# Y1BVER2_0_3.net
KiCad netlist of a schematic drawn in Altium Designer
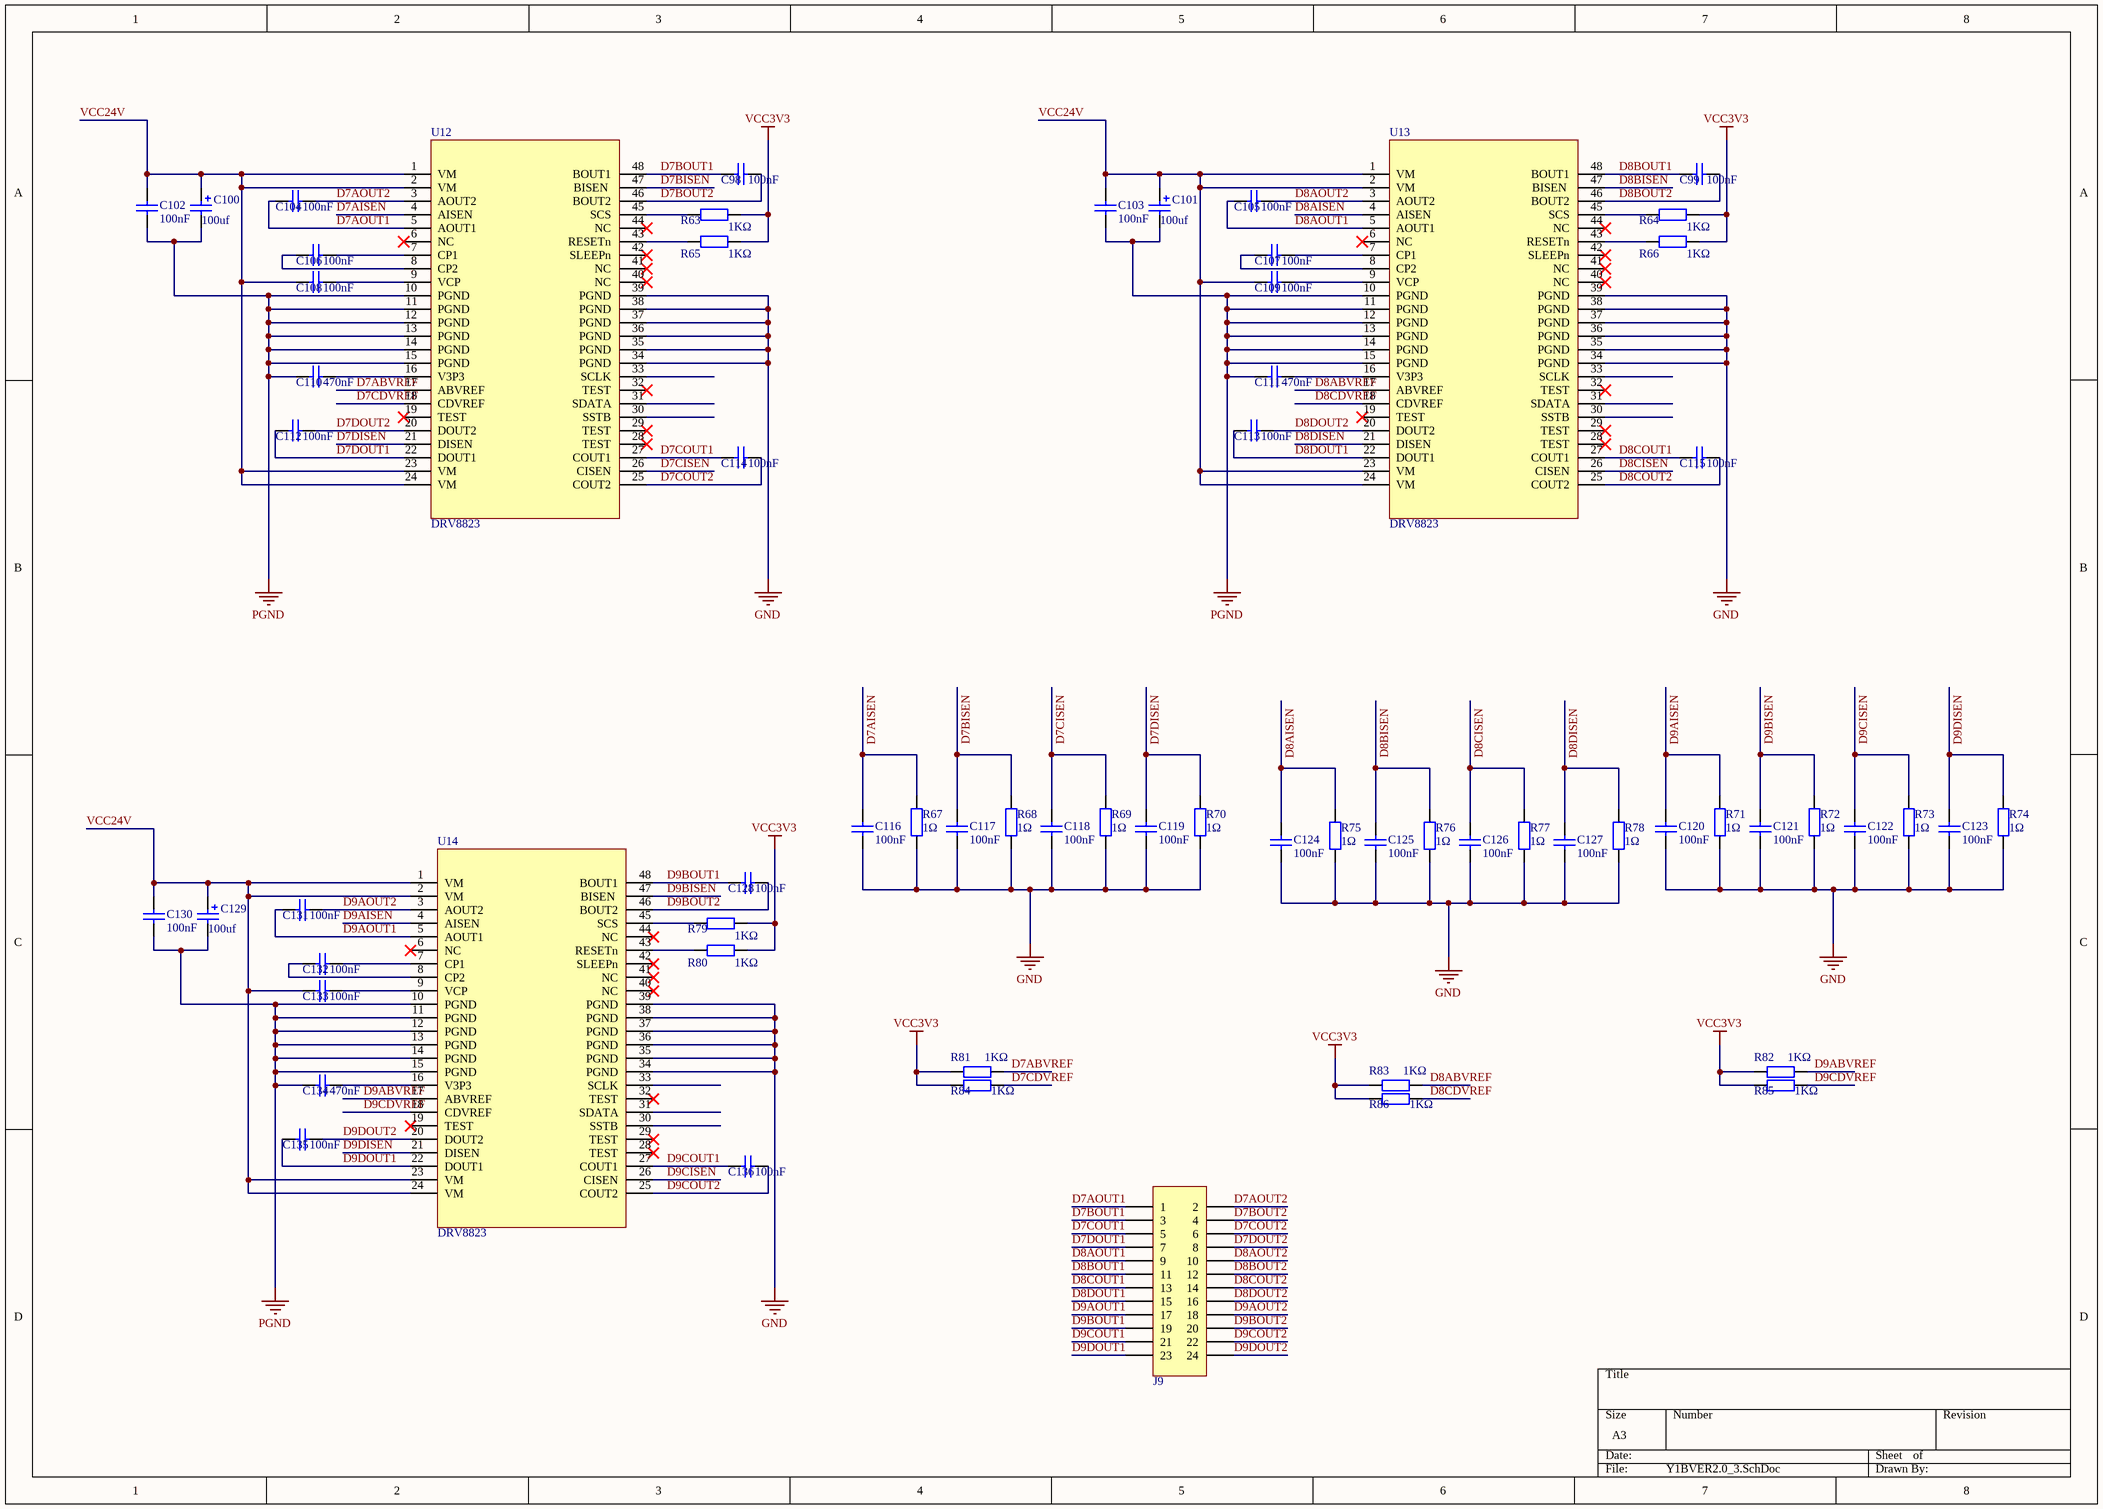
[diagram p0: Y1BVER2.0_3.SchDoc]

(export (version "E")
  (design (tool "Eeschema 10.0.6"))
  (components
    (comp (ref "C98")
      (value "100nF")
      (footprint "0603_C")
      (description "贴片电容")
      (libsource (lib "AD封装2018.9.19Miscellaneous Devices LC") (part "0603 100nF (104) 10% 50V"))
    )
    (comp (ref "C99")
      (value "100nF")
      (footprint "0603_C")
      (description "贴片电容")
      (libsource (lib "AD封装2018.9.19Miscellaneous Devices LC") (part "0603 100nF (104) 10% 50V"))
    )
    (comp (ref "C100") (value "100uf") (footprint "E_6.3*5.4") (libsource (lib "我的集成库") (part "C")))
    (comp (ref "C101") (value "100uf") (footprint "E_6.3*5.4") (libsource (lib "我的集成库") (part "C")))
    (comp (ref "C102")
      (value "100nF")
      (footprint "0603_C")
      (description "贴片电容")
      (libsource (lib "AD封装2018.9.19Miscellaneous Devices LC") (part "0603 100nF (104) 10% 50V"))
    )
    (comp (ref "C103")
      (value "100nF")
      (footprint "0603_C")
      (description "贴片电容")
      (libsource (lib "AD封装2018.9.19Miscellaneous Devices LC") (part "0603 100nF (104) 10% 50V"))
    )
    (comp (ref "C104")
      (value "100nF")
      (footprint "0603_C")
      (description "贴片电容")
      (libsource (lib "AD封装2018.9.19Miscellaneous Devices LC") (part "0603 100nF (104) 10% 50V"))
    )
    (comp (ref "C105")
      (value "100nF")
      (footprint "0603_C")
      (description "贴片电容")
      (libsource (lib "AD封装2018.9.19Miscellaneous Devices LC") (part "0603 100nF (104) 10% 50V"))
    )
    (comp (ref "C106")
      (value "100nF")
      (footprint "0603_C")
      (description "贴片电容")
      (libsource (lib "AD封装2018.9.19Miscellaneous Devices LC") (part "0603 100nF (104) 10% 50V"))
    )
    (comp (ref "C107")
      (value "100nF")
      (footprint "0603_C")
      (description "贴片电容")
      (libsource (lib "AD封装2018.9.19Miscellaneous Devices LC") (part "0603 100nF (104) 10% 50V"))
    )
    (comp (ref "C108")
      (value "100nF")
      (footprint "0603_C")
      (description "贴片电容")
      (libsource (lib "AD封装2018.9.19Miscellaneous Devices LC") (part "0603 100nF (104) 10% 50V"))
    )
    (comp (ref "C109")
      (value "100nF")
      (footprint "0603_C")
      (description "贴片电容")
      (libsource (lib "AD封装2018.9.19Miscellaneous Devices LC") (part "0603 100nF (104) 10% 50V"))
    )
    (comp (ref "C110")
      (value "470nF")
      (footprint "0603_C")
      (description "贴片电容")
      (libsource (lib "AD封装2018.9.19Miscellaneous Devices LC") (part "0603 470nF (474) 10% 25V"))
    )
    (comp (ref "C111")
      (value "470nF")
      (footprint "0603_C")
      (description "贴片电容")
      (libsource (lib "AD封装2018.9.19Miscellaneous Devices LC") (part "0603 470nF (474) 10% 25V"))
    )
    (comp (ref "C112")
      (value "100nF")
      (footprint "0603_C")
      (description "贴片电容")
      (libsource (lib "AD封装2018.9.19Miscellaneous Devices LC") (part "0603 100nF (104) 10% 50V"))
    )
    (comp (ref "C113")
      (value "100nF")
      (footprint "0603_C")
      (description "贴片电容")
      (libsource (lib "AD封装2018.9.19Miscellaneous Devices LC") (part "0603 100nF (104) 10% 50V"))
    )
    (comp (ref "C114")
      (value "100nF")
      (footprint "0603_C")
      (description "贴片电容")
      (libsource (lib "AD封装2018.9.19Miscellaneous Devices LC") (part "0603 100nF (104) 10% 50V"))
    )
    (comp (ref "C115")
      (value "100nF")
      (footprint "0603_C")
      (description "贴片电容")
      (libsource (lib "AD封装2018.9.19Miscellaneous Devices LC") (part "0603 100nF (104) 10% 50V"))
    )
    (comp (ref "C116")
      (value "100nF")
      (footprint "0603_C")
      (description "贴片电容")
      (libsource (lib "AD封装2018.9.19Miscellaneous Devices LC") (part "0603 100nF (104) 10% 50V"))
    )
    (comp (ref "C117")
      (value "100nF")
      (footprint "0603_C")
      (description "贴片电容")
      (libsource (lib "AD封装2018.9.19Miscellaneous Devices LC") (part "0603 100nF (104) 10% 50V"))
    )
    (comp (ref "C118")
      (value "100nF")
      (footprint "0603_C")
      (description "贴片电容")
      (libsource (lib "AD封装2018.9.19Miscellaneous Devices LC") (part "0603 100nF (104) 10% 50V"))
    )
    (comp (ref "C119")
      (value "100nF")
      (footprint "0603_C")
      (description "贴片电容")
      (libsource (lib "AD封装2018.9.19Miscellaneous Devices LC") (part "0603 100nF (104) 10% 50V"))
    )
    (comp (ref "C120")
      (value "100nF")
      (footprint "0603_C")
      (description "贴片电容")
      (libsource (lib "AD封装2018.9.19Miscellaneous Devices LC") (part "0603 100nF (104) 10% 50V"))
    )
    (comp (ref "C121")
      (value "100nF")
      (footprint "0603_C")
      (description "贴片电容")
      (libsource (lib "AD封装2018.9.19Miscellaneous Devices LC") (part "0603 100nF (104) 10% 50V"))
    )
    (comp (ref "C122")
      (value "100nF")
      (footprint "0603_C")
      (description "贴片电容")
      (libsource (lib "AD封装2018.9.19Miscellaneous Devices LC") (part "0603 100nF (104) 10% 50V"))
    )
    (comp (ref "C123")
      (value "100nF")
      (footprint "0603_C")
      (description "贴片电容")
      (libsource (lib "AD封装2018.9.19Miscellaneous Devices LC") (part "0603 100nF (104) 10% 50V"))
    )
    (comp (ref "C124")
      (value "100nF")
      (footprint "0603_C")
      (description "贴片电容")
      (libsource (lib "AD封装2018.9.19Miscellaneous Devices LC") (part "0603 100nF (104) 10% 50V"))
    )
    (comp (ref "C125")
      (value "100nF")
      (footprint "0603_C")
      (description "贴片电容")
      (libsource (lib "AD封装2018.9.19Miscellaneous Devices LC") (part "0603 100nF (104) 10% 50V"))
    )
    (comp (ref "C126")
      (value "100nF")
      (footprint "0603_C")
      (description "贴片电容")
      (libsource (lib "AD封装2018.9.19Miscellaneous Devices LC") (part "0603 100nF (104) 10% 50V"))
    )
    (comp (ref "C127")
      (value "100nF")
      (footprint "0603_C")
      (description "贴片电容")
      (libsource (lib "AD封装2018.9.19Miscellaneous Devices LC") (part "0603 100nF (104) 10% 50V"))
    )
    (comp (ref "C128")
      (value "100nF")
      (footprint "0603_C")
      (description "贴片电容")
      (libsource (lib "AD封装2018.9.19Miscellaneous Devices LC") (part "0603 100nF (104) 10% 50V"))
    )
    (comp (ref "C129") (value "100uf") (footprint "E_6.3*5.4") (libsource (lib "我的集成库") (part "C")))
    (comp (ref "C130")
      (value "100nF")
      (footprint "0603_C")
      (description "贴片电容")
      (libsource (lib "AD封装2018.9.19Miscellaneous Devices LC") (part "0603 100nF (104) 10% 50V"))
    )
    (comp (ref "C131")
      (value "100nF")
      (footprint "0603_C")
      (description "贴片电容")
      (libsource (lib "AD封装2018.9.19Miscellaneous Devices LC") (part "0603 100nF (104) 10% 50V"))
    )
    (comp (ref "C132")
      (value "100nF")
      (footprint "0603_C")
      (description "贴片电容")
      (libsource (lib "AD封装2018.9.19Miscellaneous Devices LC") (part "0603 100nF (104) 10% 50V"))
    )
    (comp (ref "C133")
      (value "100nF")
      (footprint "0603_C")
      (description "贴片电容")
      (libsource (lib "AD封装2018.9.19Miscellaneous Devices LC") (part "0603 100nF (104) 10% 50V"))
    )
    (comp (ref "C134")
      (value "470nF")
      (footprint "0603_C")
      (description "贴片电容")
      (libsource (lib "AD封装2018.9.19Miscellaneous Devices LC") (part "0603 470nF (474) 10% 25V"))
    )
    (comp (ref "C135")
      (value "100nF")
      (footprint "0603_C")
      (description "贴片电容")
      (libsource (lib "AD封装2018.9.19Miscellaneous Devices LC") (part "0603 100nF (104) 10% 50V"))
    )
    (comp (ref "C136")
      (value "100nF")
      (footprint "0603_C")
      (description "贴片电容")
      (libsource (lib "AD封装2018.9.19Miscellaneous Devices LC") (part "0603 100nF (104) 10% 50V"))
    )
    (comp (ref "J9")
      (value "header24p")
      (footprint "5557-2*12P")
      (libsource (lib "我的集成库") (part "header24p"))
    )
    (comp (ref "R63")
      (value "1KΩ")
      (footprint "0603_R")
      (description "贴片电阻")
      (libsource (lib "AD封装2018.9.19Miscellaneous Devices LC") (part "0603 1KΩ (1001) 1%"))
    )
    (comp (ref "R64")
      (value "1KΩ")
      (footprint "0603_R")
      (description "贴片电阻")
      (libsource (lib "AD封装2018.9.19Miscellaneous Devices LC") (part "0603 1KΩ (1001) 1%"))
    )
    (comp (ref "R65")
      (value "1KΩ")
      (footprint "0603_R")
      (description "贴片电阻")
      (libsource (lib "AD封装2018.9.19Miscellaneous Devices LC") (part "0603 1KΩ (1001) 1%"))
    )
    (comp (ref "R66")
      (value "1KΩ")
      (footprint "0603_R")
      (description "贴片电阻")
      (libsource (lib "AD封装2018.9.19Miscellaneous Devices LC") (part "0603 1KΩ (1001) 1%"))
    )
    (comp (ref "R67")
      (value "1Ω")
      (footprint "0603_R")
      (description "贴片电阻")
      (libsource (lib "AD封装2018.9.19Miscellaneous Devices LC") (part "0603 1Ω (1R00) 1%"))
    )
    (comp (ref "R68")
      (value "1Ω")
      (footprint "0603_R")
      (description "贴片电阻")
      (libsource (lib "AD封装2018.9.19Miscellaneous Devices LC") (part "0603 1Ω (1R00) 1%"))
    )
    (comp (ref "R69")
      (value "1Ω")
      (footprint "0603_R")
      (description "贴片电阻")
      (libsource (lib "AD封装2018.9.19Miscellaneous Devices LC") (part "0603 1Ω (1R00) 1%"))
    )
    (comp (ref "R70")
      (value "1Ω")
      (footprint "0603_R")
      (description "贴片电阻")
      (libsource (lib "AD封装2018.9.19Miscellaneous Devices LC") (part "0603 1Ω (1R00) 1%"))
    )
    (comp (ref "R71")
      (value "1Ω")
      (footprint "0603_R")
      (description "贴片电阻")
      (libsource (lib "AD封装2018.9.19Miscellaneous Devices LC") (part "0603 1Ω (1R00) 1%"))
    )
    (comp (ref "R72")
      (value "1Ω")
      (footprint "0603_R")
      (description "贴片电阻")
      (libsource (lib "AD封装2018.9.19Miscellaneous Devices LC") (part "0603 1Ω (1R00) 1%"))
    )
    (comp (ref "R73")
      (value "1Ω")
      (footprint "0603_R")
      (description "贴片电阻")
      (libsource (lib "AD封装2018.9.19Miscellaneous Devices LC") (part "0603 1Ω (1R00) 1%"))
    )
    (comp (ref "R74")
      (value "1Ω")
      (footprint "0603_R")
      (description "贴片电阻")
      (libsource (lib "AD封装2018.9.19Miscellaneous Devices LC") (part "0603 1Ω (1R00) 1%"))
    )
    (comp (ref "R75")
      (value "1Ω")
      (footprint "0603_R")
      (description "贴片电阻")
      (libsource (lib "AD封装2018.9.19Miscellaneous Devices LC") (part "0603 1Ω (1R00) 1%"))
    )
    (comp (ref "R76")
      (value "1Ω")
      (footprint "0603_R")
      (description "贴片电阻")
      (libsource (lib "AD封装2018.9.19Miscellaneous Devices LC") (part "0603 1Ω (1R00) 1%"))
    )
    (comp (ref "R77")
      (value "1Ω")
      (footprint "0603_R")
      (description "贴片电阻")
      (libsource (lib "AD封装2018.9.19Miscellaneous Devices LC") (part "0603 1Ω (1R00) 1%"))
    )
    (comp (ref "R78")
      (value "1Ω")
      (footprint "0603_R")
      (description "贴片电阻")
      (libsource (lib "AD封装2018.9.19Miscellaneous Devices LC") (part "0603 1Ω (1R00) 1%"))
    )
    (comp (ref "R79")
      (value "1KΩ")
      (footprint "0603_R")
      (description "贴片电阻")
      (libsource (lib "AD封装2018.9.19Miscellaneous Devices LC") (part "0603 1KΩ (1001) 1%"))
    )
    (comp (ref "R80")
      (value "1KΩ")
      (footprint "0603_R")
      (description "贴片电阻")
      (libsource (lib "AD封装2018.9.19Miscellaneous Devices LC") (part "0603 1KΩ (1001) 1%"))
    )
    (comp (ref "R81")
      (value "1KΩ")
      (footprint "0603_R")
      (description "贴片电阻")
      (libsource (lib "AD封装2018.9.19Miscellaneous Devices LC") (part "0603 1KΩ (1001) 1%"))
    )
    (comp (ref "R82")
      (value "1KΩ")
      (footprint "0603_R")
      (description "贴片电阻")
      (libsource (lib "AD封装2018.9.19Miscellaneous Devices LC") (part "0603 1KΩ (1001) 1%"))
    )
    (comp (ref "R83")
      (value "1KΩ")
      (footprint "0603_R")
      (description "贴片电阻")
      (libsource (lib "AD封装2018.9.19Miscellaneous Devices LC") (part "0603 1KΩ (1001) 1%"))
    )
    (comp (ref "R84")
      (value "1KΩ")
      (footprint "0603_R")
      (description "贴片电阻")
      (libsource (lib "AD封装2018.9.19Miscellaneous Devices LC") (part "0603 1KΩ (1001) 1%"))
    )
    (comp (ref "R85")
      (value "1KΩ")
      (footprint "0603_R")
      (description "贴片电阻")
      (libsource (lib "AD封装2018.9.19Miscellaneous Devices LC") (part "0603 1KΩ (1001) 1%"))
    )
    (comp (ref "R86")
      (value "1KΩ")
      (footprint "0603_R")
      (description "贴片电阻")
      (libsource (lib "AD封装2018.9.19Miscellaneous Devices LC") (part "0603 1KΩ (1001) 1%"))
    )
    (comp (ref "U12")
      (value "DRV8823")
      (footprint "HTSSOP-48")
      (description "4路BDC电机驱动")
      (libsource (lib "我的原理图库") (part "DRV8823"))
    )
    (comp (ref "U13")
      (value "DRV8823")
      (footprint "HTSSOP-48")
      (description "4路BDC电机驱动")
      (libsource (lib "我的原理图库") (part "DRV8823"))
    )
    (comp (ref "U14")
      (value "DRV8823")
      (footprint "HTSSOP-48")
      (description "4路BDC电机驱动")
      (libsource (lib "我的原理图库") (part "DRV8823"))
    )
  )
  (nets
    (net (code "1") (name "/D7ABVREF") (class "Default")
      (node (ref "R81") (pin "2") (pinfunction "2_2") (pintype "passive"))
      (node (ref "U12") (pin "17") (pinfunction "ABVREF_17") (pintype "passive"))
    )
    (net (code "2") (name "/D7AISEN") (class "Default")
      (node (ref "C116") (pin "2") (pinfunction "2_2") (pintype "passive"))
      (node (ref "R67") (pin "2") (pinfunction "2_2") (pintype "passive"))
      (node (ref "U12") (pin "4") (pinfunction "AISEN_4") (pintype "passive"))
    )
    (net (code "3") (name "/D7AOUT1") (class "Default")
      (node (ref "C104") (pin "1") (pinfunction "1_1") (pintype "passive"))
      (node (ref "J9") (pin "1") (pinfunction "1_1") (pintype "passive"))
      (node (ref "U12") (pin "5") (pinfunction "AOUT1_5") (pintype "passive"))
    )
    (net (code "4") (name "/D7AOUT2") (class "Default")
      (node (ref "C104") (pin "2") (pinfunction "2_2") (pintype "passive"))
      (node (ref "J9") (pin "2") (pinfunction "2_2") (pintype "passive"))
      (node (ref "U12") (pin "3") (pinfunction "AOUT2_3") (pintype "passive"))
    )
    (net (code "5") (name "/D7BISEN") (class "Default")
      (node (ref "C117") (pin "2") (pinfunction "2_2") (pintype "passive"))
      (node (ref "R68") (pin "2") (pinfunction "2_2") (pintype "passive"))
      (node (ref "U12") (pin "47") (pinfunction "BISEN_47") (pintype "passive"))
    )
    (net (code "6") (name "/D7BOUT1") (class "Default")
      (node (ref "C98") (pin "1") (pinfunction "1_1") (pintype "passive"))
      (node (ref "J9") (pin "3") (pinfunction "3_3") (pintype "passive"))
      (node (ref "U12") (pin "48") (pinfunction "BOUT1_48") (pintype "passive"))
    )
    (net (code "7") (name "/D7BOUT2") (class "Default")
      (node (ref "C98") (pin "2") (pinfunction "2_2") (pintype "passive"))
      (node (ref "J9") (pin "4") (pinfunction "4_4") (pintype "passive"))
      (node (ref "U12") (pin "46") (pinfunction "BOUT2_46") (pintype "passive"))
    )
    (net (code "8") (name "/D7CDVREF") (class "Default")
      (node (ref "R84") (pin "2") (pinfunction "2_2") (pintype "passive"))
      (node (ref "U12") (pin "18") (pinfunction "CDVREF_18") (pintype "passive"))
    )
    (net (code "9") (name "/D7CISEN") (class "Default")
      (node (ref "C118") (pin "2") (pinfunction "2_2") (pintype "passive"))
      (node (ref "R69") (pin "2") (pinfunction "2_2") (pintype "passive"))
      (node (ref "U12") (pin "26") (pinfunction "CISEN_26") (pintype "passive"))
    )
    (net (code "10") (name "/D7COUT1") (class "Default")
      (node (ref "C114") (pin "1") (pinfunction "1_1") (pintype "passive"))
      (node (ref "J9") (pin "5") (pinfunction "5_5") (pintype "passive"))
      (node (ref "U12") (pin "27") (pinfunction "COUT1_27") (pintype "passive"))
    )
    (net (code "11") (name "/D7COUT2") (class "Default")
      (node (ref "C114") (pin "2") (pinfunction "2_2") (pintype "passive"))
      (node (ref "J9") (pin "6") (pinfunction "6_6") (pintype "passive"))
      (node (ref "U12") (pin "25") (pinfunction "COUT2_25") (pintype "passive"))
    )
    (net (code "12") (name "/D7DISEN") (class "Default")
      (node (ref "C119") (pin "2") (pinfunction "2_2") (pintype "passive"))
      (node (ref "R70") (pin "2") (pinfunction "2_2") (pintype "passive"))
      (node (ref "U12") (pin "21") (pinfunction "DISEN_21") (pintype "passive"))
    )
    (net (code "13") (name "/D7DOUT1") (class "Default")
      (node (ref "C112") (pin "1") (pinfunction "1_1") (pintype "passive"))
      (node (ref "J9") (pin "7") (pinfunction "7_7") (pintype "passive"))
      (node (ref "U12") (pin "22") (pinfunction "DOUT1_22") (pintype "passive"))
    )
    (net (code "14") (name "/D7DOUT2") (class "Default")
      (node (ref "C112") (pin "2") (pinfunction "2_2") (pintype "passive"))
      (node (ref "J9") (pin "8") (pinfunction "8_8") (pintype "passive"))
      (node (ref "U12") (pin "20") (pinfunction "DOUT2_20") (pintype "passive"))
    )
    (net (code "15") (name "/D8ABVREF") (class "Default")
      (node (ref "R83") (pin "2") (pinfunction "2_2") (pintype "passive"))
      (node (ref "U13") (pin "17") (pinfunction "ABVREF_17") (pintype "passive"))
    )
    (net (code "16") (name "/D8AISEN") (class "Default")
      (node (ref "C124") (pin "2") (pinfunction "2_2") (pintype "passive"))
      (node (ref "R75") (pin "2") (pinfunction "2_2") (pintype "passive"))
      (node (ref "U13") (pin "4") (pinfunction "AISEN_4") (pintype "passive"))
    )
    (net (code "17") (name "/D8AOUT1") (class "Default")
      (node (ref "C105") (pin "1") (pinfunction "1_1") (pintype "passive"))
      (node (ref "J9") (pin "9") (pinfunction "9_9") (pintype "passive"))
      (node (ref "U13") (pin "5") (pinfunction "AOUT1_5") (pintype "passive"))
    )
    (net (code "18") (name "/D8AOUT2") (class "Default")
      (node (ref "C105") (pin "2") (pinfunction "2_2") (pintype "passive"))
      (node (ref "J9") (pin "10") (pinfunction "10_10") (pintype "passive"))
      (node (ref "U13") (pin "3") (pinfunction "AOUT2_3") (pintype "passive"))
    )
    (net (code "19") (name "/D8BISEN") (class "Default")
      (node (ref "C125") (pin "2") (pinfunction "2_2") (pintype "passive"))
      (node (ref "R76") (pin "2") (pinfunction "2_2") (pintype "passive"))
      (node (ref "U13") (pin "47") (pinfunction "BISEN_47") (pintype "passive"))
    )
    (net (code "20") (name "/D8BOUT1") (class "Default")
      (node (ref "C99") (pin "1") (pinfunction "1_1") (pintype "passive"))
      (node (ref "J9") (pin "11") (pinfunction "11_11") (pintype "passive"))
      (node (ref "U13") (pin "48") (pinfunction "BOUT1_48") (pintype "passive"))
    )
    (net (code "21") (name "/D8BOUT2") (class "Default")
      (node (ref "C99") (pin "2") (pinfunction "2_2") (pintype "passive"))
      (node (ref "J9") (pin "12") (pinfunction "12_12") (pintype "passive"))
      (node (ref "U13") (pin "46") (pinfunction "BOUT2_46") (pintype "passive"))
    )
    (net (code "22") (name "/D8CDVREF") (class "Default")
      (node (ref "R86") (pin "2") (pinfunction "2_2") (pintype "passive"))
      (node (ref "U13") (pin "18") (pinfunction "CDVREF_18") (pintype "passive"))
    )
    (net (code "23") (name "/D8CISEN") (class "Default")
      (node (ref "C126") (pin "2") (pinfunction "2_2") (pintype "passive"))
      (node (ref "R77") (pin "2") (pinfunction "2_2") (pintype "passive"))
      (node (ref "U13") (pin "26") (pinfunction "CISEN_26") (pintype "passive"))
    )
    (net (code "24") (name "/D8COUT1") (class "Default")
      (node (ref "C115") (pin "1") (pinfunction "1_1") (pintype "passive"))
      (node (ref "J9") (pin "13") (pinfunction "13_13") (pintype "passive"))
      (node (ref "U13") (pin "27") (pinfunction "COUT1_27") (pintype "passive"))
    )
    (net (code "25") (name "/D8COUT2") (class "Default")
      (node (ref "C115") (pin "2") (pinfunction "2_2") (pintype "passive"))
      (node (ref "J9") (pin "14") (pinfunction "14_14") (pintype "passive"))
      (node (ref "U13") (pin "25") (pinfunction "COUT2_25") (pintype "passive"))
    )
    (net (code "26") (name "/D8DISEN") (class "Default")
      (node (ref "C127") (pin "2") (pinfunction "2_2") (pintype "passive"))
      (node (ref "R78") (pin "2") (pinfunction "2_2") (pintype "passive"))
      (node (ref "U13") (pin "21") (pinfunction "DISEN_21") (pintype "passive"))
    )
    (net (code "27") (name "/D8DOUT1") (class "Default")
      (node (ref "C113") (pin "1") (pinfunction "1_1") (pintype "passive"))
      (node (ref "J9") (pin "15") (pinfunction "15_15") (pintype "passive"))
      (node (ref "U13") (pin "22") (pinfunction "DOUT1_22") (pintype "passive"))
    )
    (net (code "28") (name "/D8DOUT2") (class "Default")
      (node (ref "C113") (pin "2") (pinfunction "2_2") (pintype "passive"))
      (node (ref "J9") (pin "16") (pinfunction "16_16") (pintype "passive"))
      (node (ref "U13") (pin "20") (pinfunction "DOUT2_20") (pintype "passive"))
    )
    (net (code "29") (name "/D9ABVREF") (class "Default")
      (node (ref "R82") (pin "2") (pinfunction "2_2") (pintype "passive"))
      (node (ref "U14") (pin "17") (pinfunction "ABVREF_17") (pintype "passive"))
    )
    (net (code "30") (name "/D9AISEN") (class "Default")
      (node (ref "C120") (pin "2") (pinfunction "2_2") (pintype "passive"))
      (node (ref "R71") (pin "2") (pinfunction "2_2") (pintype "passive"))
      (node (ref "U14") (pin "4") (pinfunction "AISEN_4") (pintype "passive"))
    )
    (net (code "31") (name "/D9AOUT1") (class "Default")
      (node (ref "C131") (pin "1") (pinfunction "1_1") (pintype "passive"))
      (node (ref "J9") (pin "17") (pinfunction "17_17") (pintype "passive"))
      (node (ref "U14") (pin "5") (pinfunction "AOUT1_5") (pintype "passive"))
    )
    (net (code "32") (name "/D9AOUT2") (class "Default")
      (node (ref "C131") (pin "2") (pinfunction "2_2") (pintype "passive"))
      (node (ref "J9") (pin "18") (pinfunction "18_18") (pintype "passive"))
      (node (ref "U14") (pin "3") (pinfunction "AOUT2_3") (pintype "passive"))
    )
    (net (code "33") (name "/D9BISEN") (class "Default")
      (node (ref "C121") (pin "2") (pinfunction "2_2") (pintype "passive"))
      (node (ref "R72") (pin "2") (pinfunction "2_2") (pintype "passive"))
      (node (ref "U14") (pin "47") (pinfunction "BISEN_47") (pintype "passive"))
    )
    (net (code "34") (name "/D9BOUT1") (class "Default")
      (node (ref "C128") (pin "1") (pinfunction "1_1") (pintype "passive"))
      (node (ref "J9") (pin "19") (pinfunction "19_19") (pintype "passive"))
      (node (ref "U14") (pin "48") (pinfunction "BOUT1_48") (pintype "passive"))
    )
    (net (code "35") (name "/D9BOUT2") (class "Default")
      (node (ref "C128") (pin "2") (pinfunction "2_2") (pintype "passive"))
      (node (ref "J9") (pin "20") (pinfunction "20_20") (pintype "passive"))
      (node (ref "U14") (pin "46") (pinfunction "BOUT2_46") (pintype "passive"))
    )
    (net (code "36") (name "/D9CDVREF") (class "Default")
      (node (ref "R85") (pin "2") (pinfunction "2_2") (pintype "passive"))
      (node (ref "U14") (pin "18") (pinfunction "CDVREF_18") (pintype "passive"))
    )
    (net (code "37") (name "/D9CISEN") (class "Default")
      (node (ref "C122") (pin "2") (pinfunction "2_2") (pintype "passive"))
      (node (ref "R73") (pin "2") (pinfunction "2_2") (pintype "passive"))
      (node (ref "U14") (pin "26") (pinfunction "CISEN_26") (pintype "passive"))
    )
    (net (code "38") (name "/D9COUT1") (class "Default")
      (node (ref "C136") (pin "1") (pinfunction "1_1") (pintype "passive"))
      (node (ref "J9") (pin "21") (pinfunction "21_21") (pintype "passive"))
      (node (ref "U14") (pin "27") (pinfunction "COUT1_27") (pintype "passive"))
    )
    (net (code "39") (name "/D9COUT2") (class "Default")
      (node (ref "C136") (pin "2") (pinfunction "2_2") (pintype "passive"))
      (node (ref "J9") (pin "22") (pinfunction "22_22") (pintype "passive"))
      (node (ref "U14") (pin "25") (pinfunction "COUT2_25") (pintype "passive"))
    )
    (net (code "40") (name "/D9DISEN") (class "Default")
      (node (ref "C123") (pin "2") (pinfunction "2_2") (pintype "passive"))
      (node (ref "R74") (pin "2") (pinfunction "2_2") (pintype "passive"))
      (node (ref "U14") (pin "21") (pinfunction "DISEN_21") (pintype "passive"))
    )
    (net (code "41") (name "/D9DOUT1") (class "Default")
      (node (ref "C135") (pin "1") (pinfunction "1_1") (pintype "passive"))
      (node (ref "J9") (pin "23") (pinfunction "23_23") (pintype "passive"))
      (node (ref "U14") (pin "22") (pinfunction "DOUT1_22") (pintype "passive"))
    )
    (net (code "42") (name "/D9DOUT2") (class "Default")
      (node (ref "C135") (pin "2") (pinfunction "2_2") (pintype "passive"))
      (node (ref "J9") (pin "24") (pinfunction "24_24") (pintype "passive"))
      (node (ref "U14") (pin "20") (pinfunction "DOUT2_20") (pintype "passive"))
    )
    (net (code "43") (name "/VCC24V") (class "Default")
      (node (ref "C100") (pin "1") (pinfunction "1_1") (pintype "passive"))
      (node (ref "C101") (pin "1") (pinfunction "1_1") (pintype "passive"))
      (node (ref "C102") (pin "2") (pinfunction "2_2") (pintype "passive"))
      (node (ref "C103") (pin "2") (pinfunction "2_2") (pintype "passive"))
      (node (ref "C108") (pin "1") (pinfunction "1_1") (pintype "passive"))
      (node (ref "C109") (pin "1") (pinfunction "1_1") (pintype "passive"))
      (node (ref "C129") (pin "1") (pinfunction "1_1") (pintype "passive"))
      (node (ref "C130") (pin "2") (pinfunction "2_2") (pintype "passive"))
      (node (ref "C133") (pin "1") (pinfunction "1_1") (pintype "passive"))
      (node (ref "U12") (pin "1") (pinfunction "VM_1") (pintype "passive"))
      (node (ref "U12") (pin "2") (pinfunction "VM_2") (pintype "passive"))
      (node (ref "U12") (pin "23") (pinfunction "VM_23") (pintype "passive"))
      (node (ref "U12") (pin "24") (pinfunction "VM_24") (pintype "passive"))
      (node (ref "U13") (pin "1") (pinfunction "VM_1") (pintype "passive"))
      (node (ref "U13") (pin "2") (pinfunction "VM_2") (pintype "passive"))
      (node (ref "U13") (pin "23") (pinfunction "VM_23") (pintype "passive"))
      (node (ref "U13") (pin "24") (pinfunction "VM_24") (pintype "passive"))
      (node (ref "U14") (pin "1") (pinfunction "VM_1") (pintype "passive"))
      (node (ref "U14") (pin "2") (pinfunction "VM_2") (pintype "passive"))
      (node (ref "U14") (pin "23") (pinfunction "VM_23") (pintype "passive"))
      (node (ref "U14") (pin "24") (pinfunction "VM_24") (pintype "passive"))
    )
    (net (code "44") (name "GND") (class "Default")
      (node (ref "C116") (pin "1") (pinfunction "1_1") (pintype "passive"))
      (node (ref "C117") (pin "1") (pinfunction "1_1") (pintype "passive"))
      (node (ref "C118") (pin "1") (pinfunction "1_1") (pintype "passive"))
      (node (ref "C119") (pin "1") (pinfunction "1_1") (pintype "passive"))
      (node (ref "C120") (pin "1") (pinfunction "1_1") (pintype "passive"))
      (node (ref "C121") (pin "1") (pinfunction "1_1") (pintype "passive"))
      (node (ref "C122") (pin "1") (pinfunction "1_1") (pintype "passive"))
      (node (ref "C123") (pin "1") (pinfunction "1_1") (pintype "passive"))
      (node (ref "C124") (pin "1") (pinfunction "1_1") (pintype "passive"))
      (node (ref "C125") (pin "1") (pinfunction "1_1") (pintype "passive"))
      (node (ref "C126") (pin "1") (pinfunction "1_1") (pintype "passive"))
      (node (ref "C127") (pin "1") (pinfunction "1_1") (pintype "passive"))
      (node (ref "R67") (pin "1") (pinfunction "1_1") (pintype "passive"))
      (node (ref "R68") (pin "1") (pinfunction "1_1") (pintype "passive"))
      (node (ref "R69") (pin "1") (pinfunction "1_1") (pintype "passive"))
      (node (ref "R70") (pin "1") (pinfunction "1_1") (pintype "passive"))
      (node (ref "R71") (pin "1") (pinfunction "1_1") (pintype "passive"))
      (node (ref "R72") (pin "1") (pinfunction "1_1") (pintype "passive"))
      (node (ref "R73") (pin "1") (pinfunction "1_1") (pintype "passive"))
      (node (ref "R74") (pin "1") (pinfunction "1_1") (pintype "passive"))
      (node (ref "R75") (pin "1") (pinfunction "1_1") (pintype "passive"))
      (node (ref "R76") (pin "1") (pinfunction "1_1") (pintype "passive"))
      (node (ref "R77") (pin "1") (pinfunction "1_1") (pintype "passive"))
      (node (ref "R78") (pin "1") (pinfunction "1_1") (pintype "passive"))
      (node (ref "U12") (pin "34") (pinfunction "PGND_34") (pintype "passive"))
      (node (ref "U12") (pin "35") (pinfunction "PGND_35") (pintype "passive"))
      (node (ref "U12") (pin "36") (pinfunction "PGND_36") (pintype "passive"))
      (node (ref "U12") (pin "37") (pinfunction "PGND_37") (pintype "passive"))
      (node (ref "U12") (pin "38") (pinfunction "PGND_38") (pintype "passive"))
      (node (ref "U12") (pin "39") (pinfunction "PGND_39") (pintype "passive"))
      (node (ref "U13") (pin "34") (pinfunction "PGND_34") (pintype "passive"))
      (node (ref "U13") (pin "35") (pinfunction "PGND_35") (pintype "passive"))
      (node (ref "U13") (pin "36") (pinfunction "PGND_36") (pintype "passive"))
      (node (ref "U13") (pin "37") (pinfunction "PGND_37") (pintype "passive"))
      (node (ref "U13") (pin "38") (pinfunction "PGND_38") (pintype "passive"))
      (node (ref "U13") (pin "39") (pinfunction "PGND_39") (pintype "passive"))
      (node (ref "U14") (pin "34") (pinfunction "PGND_34") (pintype "passive"))
      (node (ref "U14") (pin "35") (pinfunction "PGND_35") (pintype "passive"))
      (node (ref "U14") (pin "36") (pinfunction "PGND_36") (pintype "passive"))
      (node (ref "U14") (pin "37") (pinfunction "PGND_37") (pintype "passive"))
      (node (ref "U14") (pin "38") (pinfunction "PGND_38") (pintype "passive"))
      (node (ref "U14") (pin "39") (pinfunction "PGND_39") (pintype "passive"))
    )
    (net (code "45") (name "Net-(U12-CP1)") (class "Default")
      (node (ref "C106") (pin "2") (pinfunction "2_2") (pintype "passive"))
      (node (ref "U12") (pin "7") (pinfunction "CP1_7") (pintype "passive"))
    )
    (net (code "46") (name "Net-(U12-CP2)") (class "Default")
      (node (ref "C106") (pin "1") (pinfunction "1_1") (pintype "passive"))
      (node (ref "U12") (pin "8") (pinfunction "CP2_8") (pintype "passive"))
    )
    (net (code "47") (name "Net-(U12-RESETn)") (class "Default")
      (node (ref "R65") (pin "1") (pinfunction "1_1") (pintype "passive"))
      (node (ref "U12") (pin "43") (pinfunction "RESETn_43") (pintype "passive"))
    )
    (net (code "48") (name "Net-(U12-SCS)") (class "Default")
      (node (ref "R63") (pin "1") (pinfunction "1_1") (pintype "passive"))
      (node (ref "U12") (pin "45") (pinfunction "SCS_45") (pintype "passive"))
    )
    (net (code "49") (name "Net-(U12-V3P3)") (class "Default")
      (node (ref "C110") (pin "2") (pinfunction "2_2") (pintype "passive"))
      (node (ref "U12") (pin "16") (pinfunction "V3P3_16") (pintype "passive"))
    )
    (net (code "50") (name "Net-(U12-VCP)") (class "Default")
      (node (ref "C108") (pin "2") (pinfunction "2_2") (pintype "passive"))
      (node (ref "U12") (pin "9") (pinfunction "VCP_9") (pintype "passive"))
    )
    (net (code "51") (name "Net-(U13-CP1)") (class "Default")
      (node (ref "C107") (pin "2") (pinfunction "2_2") (pintype "passive"))
      (node (ref "U13") (pin "7") (pinfunction "CP1_7") (pintype "passive"))
    )
    (net (code "52") (name "Net-(U13-CP2)") (class "Default")
      (node (ref "C107") (pin "1") (pinfunction "1_1") (pintype "passive"))
      (node (ref "U13") (pin "8") (pinfunction "CP2_8") (pintype "passive"))
    )
    (net (code "53") (name "Net-(U13-RESETn)") (class "Default")
      (node (ref "R66") (pin "1") (pinfunction "1_1") (pintype "passive"))
      (node (ref "U13") (pin "43") (pinfunction "RESETn_43") (pintype "passive"))
    )
    (net (code "54") (name "Net-(U13-SCS)") (class "Default")
      (node (ref "R64") (pin "1") (pinfunction "1_1") (pintype "passive"))
      (node (ref "U13") (pin "45") (pinfunction "SCS_45") (pintype "passive"))
    )
    (net (code "55") (name "Net-(U13-V3P3)") (class "Default")
      (node (ref "C111") (pin "2") (pinfunction "2_2") (pintype "passive"))
      (node (ref "U13") (pin "16") (pinfunction "V3P3_16") (pintype "passive"))
    )
    (net (code "56") (name "Net-(U13-VCP)") (class "Default")
      (node (ref "C109") (pin "2") (pinfunction "2_2") (pintype "passive"))
      (node (ref "U13") (pin "9") (pinfunction "VCP_9") (pintype "passive"))
    )
    (net (code "57") (name "Net-(U14-CP1)") (class "Default")
      (node (ref "C132") (pin "2") (pinfunction "2_2") (pintype "passive"))
      (node (ref "U14") (pin "7") (pinfunction "CP1_7") (pintype "passive"))
    )
    (net (code "58") (name "Net-(U14-CP2)") (class "Default")
      (node (ref "C132") (pin "1") (pinfunction "1_1") (pintype "passive"))
      (node (ref "U14") (pin "8") (pinfunction "CP2_8") (pintype "passive"))
    )
    (net (code "59") (name "Net-(U14-RESETn)") (class "Default")
      (node (ref "R80") (pin "1") (pinfunction "1_1") (pintype "passive"))
      (node (ref "U14") (pin "43") (pinfunction "RESETn_43") (pintype "passive"))
    )
    (net (code "60") (name "Net-(U14-SCS)") (class "Default")
      (node (ref "R79") (pin "1") (pinfunction "1_1") (pintype "passive"))
      (node (ref "U14") (pin "45") (pinfunction "SCS_45") (pintype "passive"))
    )
    (net (code "61") (name "Net-(U14-V3P3)") (class "Default")
      (node (ref "C134") (pin "2") (pinfunction "2_2") (pintype "passive"))
      (node (ref "U14") (pin "16") (pinfunction "V3P3_16") (pintype "passive"))
    )
    (net (code "62") (name "Net-(U14-VCP)") (class "Default")
      (node (ref "C133") (pin "2") (pinfunction "2_2") (pintype "passive"))
      (node (ref "U14") (pin "9") (pinfunction "VCP_9") (pintype "passive"))
    )
    (net (code "63") (name "PGND") (class "Default")
      (node (ref "C100") (pin "2") (pinfunction "2_2") (pintype "passive"))
      (node (ref "C101") (pin "2") (pinfunction "2_2") (pintype "passive"))
      (node (ref "C102") (pin "1") (pinfunction "1_1") (pintype "passive"))
      (node (ref "C103") (pin "1") (pinfunction "1_1") (pintype "passive"))
      (node (ref "C110") (pin "1") (pinfunction "1_1") (pintype "passive"))
      (node (ref "C111") (pin "1") (pinfunction "1_1") (pintype "passive"))
      (node (ref "C129") (pin "2") (pinfunction "2_2") (pintype "passive"))
      (node (ref "C130") (pin "1") (pinfunction "1_1") (pintype "passive"))
      (node (ref "C134") (pin "1") (pinfunction "1_1") (pintype "passive"))
      (node (ref "U12") (pin "10") (pinfunction "PGND_10") (pintype "passive"))
      (node (ref "U12") (pin "11") (pinfunction "PGND_11") (pintype "passive"))
      (node (ref "U12") (pin "12") (pinfunction "PGND_12") (pintype "passive"))
      (node (ref "U12") (pin "13") (pinfunction "PGND_13") (pintype "passive"))
      (node (ref "U12") (pin "14") (pinfunction "PGND_14") (pintype "passive"))
      (node (ref "U12") (pin "15") (pinfunction "PGND_15") (pintype "passive"))
      (node (ref "U13") (pin "10") (pinfunction "PGND_10") (pintype "passive"))
      (node (ref "U13") (pin "11") (pinfunction "PGND_11") (pintype "passive"))
      (node (ref "U13") (pin "12") (pinfunction "PGND_12") (pintype "passive"))
      (node (ref "U13") (pin "13") (pinfunction "PGND_13") (pintype "passive"))
      (node (ref "U13") (pin "14") (pinfunction "PGND_14") (pintype "passive"))
      (node (ref "U13") (pin "15") (pinfunction "PGND_15") (pintype "passive"))
      (node (ref "U14") (pin "10") (pinfunction "PGND_10") (pintype "passive"))
      (node (ref "U14") (pin "11") (pinfunction "PGND_11") (pintype "passive"))
      (node (ref "U14") (pin "12") (pinfunction "PGND_12") (pintype "passive"))
      (node (ref "U14") (pin "13") (pinfunction "PGND_13") (pintype "passive"))
      (node (ref "U14") (pin "14") (pinfunction "PGND_14") (pintype "passive"))
      (node (ref "U14") (pin "15") (pinfunction "PGND_15") (pintype "passive"))
    )
    (net (code "64") (name "VCC3V3") (class "Default")
      (node (ref "R63") (pin "2") (pinfunction "2_2") (pintype "passive"))
      (node (ref "R64") (pin "2") (pinfunction "2_2") (pintype "passive"))
      (node (ref "R65") (pin "2") (pinfunction "2_2") (pintype "passive"))
      (node (ref "R66") (pin "2") (pinfunction "2_2") (pintype "passive"))
      (node (ref "R79") (pin "2") (pinfunction "2_2") (pintype "passive"))
      (node (ref "R80") (pin "2") (pinfunction "2_2") (pintype "passive"))
      (node (ref "R81") (pin "1") (pinfunction "1_1") (pintype "passive"))
      (node (ref "R82") (pin "1") (pinfunction "1_1") (pintype "passive"))
      (node (ref "R83") (pin "1") (pinfunction "1_1") (pintype "passive"))
      (node (ref "R84") (pin "1") (pinfunction "1_1") (pintype "passive"))
      (node (ref "R85") (pin "1") (pinfunction "1_1") (pintype "passive"))
      (node (ref "R86") (pin "1") (pinfunction "1_1") (pintype "passive"))
    )
    (net (code "65") (name "unconnected-(U12-NC-Pad6)") (class "Default")
      (node (ref "U12") (pin "6") (pinfunction "NC_6") (pintype "passive+no_connect"))
    )
    (net (code "66") (name "unconnected-(U12-NC-Pad40)") (class "Default")
      (node (ref "U12") (pin "40") (pinfunction "NC_40") (pintype "passive+no_connect"))
    )
    (net (code "67") (name "unconnected-(U12-NC-Pad41)") (class "Default")
      (node (ref "U12") (pin "41") (pinfunction "NC_41") (pintype "passive+no_connect"))
    )
    (net (code "68") (name "unconnected-(U12-NC-Pad44)") (class "Default")
      (node (ref "U12") (pin "44") (pinfunction "NC_44") (pintype "passive+no_connect"))
    )
    (net (code "69") (name "unconnected-(U12-SCLK-Pad33)") (class "Default")
      (node (ref "U12") (pin "33") (pinfunction "SCLK_33") (pintype "passive"))
    )
    (net (code "70") (name "unconnected-(U12-SDATA-Pad31)") (class "Default")
      (node (ref "U12") (pin "31") (pinfunction "SDATA_31") (pintype "passive"))
    )
    (net (code "71") (name "unconnected-(U12-SLEEPn-Pad42)") (class "Default")
      (node (ref "U12") (pin "42") (pinfunction "SLEEPn_42") (pintype "passive+no_connect"))
    )
    (net (code "72") (name "unconnected-(U12-SSTB-Pad30)") (class "Default")
      (node (ref "U12") (pin "30") (pinfunction "SSTB_30") (pintype "passive"))
    )
    (net (code "73") (name "unconnected-(U12-TEST-Pad19)") (class "Default")
      (node (ref "U12") (pin "19") (pinfunction "TEST_19") (pintype "passive+no_connect"))
    )
    (net (code "74") (name "unconnected-(U12-TEST-Pad28)") (class "Default")
      (node (ref "U12") (pin "28") (pinfunction "TEST_28") (pintype "passive+no_connect"))
    )
    (net (code "75") (name "unconnected-(U12-TEST-Pad29)") (class "Default")
      (node (ref "U12") (pin "29") (pinfunction "TEST_29") (pintype "passive+no_connect"))
    )
    (net (code "76") (name "unconnected-(U12-TEST-Pad32)") (class "Default")
      (node (ref "U12") (pin "32") (pinfunction "TEST_32") (pintype "passive+no_connect"))
    )
    (net (code "77") (name "unconnected-(U13-NC-Pad6)") (class "Default")
      (node (ref "U13") (pin "6") (pinfunction "NC_6") (pintype "passive+no_connect"))
    )
    (net (code "78") (name "unconnected-(U13-NC-Pad40)") (class "Default")
      (node (ref "U13") (pin "40") (pinfunction "NC_40") (pintype "passive+no_connect"))
    )
    (net (code "79") (name "unconnected-(U13-NC-Pad41)") (class "Default")
      (node (ref "U13") (pin "41") (pinfunction "NC_41") (pintype "passive+no_connect"))
    )
    (net (code "80") (name "unconnected-(U13-NC-Pad44)") (class "Default")
      (node (ref "U13") (pin "44") (pinfunction "NC_44") (pintype "passive+no_connect"))
    )
    (net (code "81") (name "unconnected-(U13-SCLK-Pad33)") (class "Default")
      (node (ref "U13") (pin "33") (pinfunction "SCLK_33") (pintype "passive"))
    )
    (net (code "82") (name "unconnected-(U13-SDATA-Pad31)") (class "Default")
      (node (ref "U13") (pin "31") (pinfunction "SDATA_31") (pintype "passive"))
    )
    (net (code "83") (name "unconnected-(U13-SLEEPn-Pad42)") (class "Default")
      (node (ref "U13") (pin "42") (pinfunction "SLEEPn_42") (pintype "passive+no_connect"))
    )
    (net (code "84") (name "unconnected-(U13-SSTB-Pad30)") (class "Default")
      (node (ref "U13") (pin "30") (pinfunction "SSTB_30") (pintype "passive"))
    )
    (net (code "85") (name "unconnected-(U13-TEST-Pad19)") (class "Default")
      (node (ref "U13") (pin "19") (pinfunction "TEST_19") (pintype "passive+no_connect"))
    )
    (net (code "86") (name "unconnected-(U13-TEST-Pad28)") (class "Default")
      (node (ref "U13") (pin "28") (pinfunction "TEST_28") (pintype "passive+no_connect"))
    )
    (net (code "87") (name "unconnected-(U13-TEST-Pad29)") (class "Default")
      (node (ref "U13") (pin "29") (pinfunction "TEST_29") (pintype "passive+no_connect"))
    )
    (net (code "88") (name "unconnected-(U13-TEST-Pad32)") (class "Default")
      (node (ref "U13") (pin "32") (pinfunction "TEST_32") (pintype "passive+no_connect"))
    )
    (net (code "89") (name "unconnected-(U14-NC-Pad6)") (class "Default")
      (node (ref "U14") (pin "6") (pinfunction "NC_6") (pintype "passive+no_connect"))
    )
    (net (code "90") (name "unconnected-(U14-NC-Pad40)") (class "Default")
      (node (ref "U14") (pin "40") (pinfunction "NC_40") (pintype "passive+no_connect"))
    )
    (net (code "91") (name "unconnected-(U14-NC-Pad41)") (class "Default")
      (node (ref "U14") (pin "41") (pinfunction "NC_41") (pintype "passive+no_connect"))
    )
    (net (code "92") (name "unconnected-(U14-NC-Pad44)") (class "Default")
      (node (ref "U14") (pin "44") (pinfunction "NC_44") (pintype "passive+no_connect"))
    )
    (net (code "93") (name "unconnected-(U14-SCLK-Pad33)") (class "Default")
      (node (ref "U14") (pin "33") (pinfunction "SCLK_33") (pintype "passive"))
    )
    (net (code "94") (name "unconnected-(U14-SDATA-Pad31)") (class "Default")
      (node (ref "U14") (pin "31") (pinfunction "SDATA_31") (pintype "passive"))
    )
    (net (code "95") (name "unconnected-(U14-SLEEPn-Pad42)") (class "Default")
      (node (ref "U14") (pin "42") (pinfunction "SLEEPn_42") (pintype "passive+no_connect"))
    )
    (net (code "96") (name "unconnected-(U14-SSTB-Pad30)") (class "Default")
      (node (ref "U14") (pin "30") (pinfunction "SSTB_30") (pintype "passive"))
    )
    (net (code "97") (name "unconnected-(U14-TEST-Pad19)") (class "Default")
      (node (ref "U14") (pin "19") (pinfunction "TEST_19") (pintype "passive+no_connect"))
    )
    (net (code "98") (name "unconnected-(U14-TEST-Pad28)") (class "Default")
      (node (ref "U14") (pin "28") (pinfunction "TEST_28") (pintype "passive+no_connect"))
    )
    (net (code "99") (name "unconnected-(U14-TEST-Pad29)") (class "Default")
      (node (ref "U14") (pin "29") (pinfunction "TEST_29") (pintype "passive+no_connect"))
    )
    (net (code "100") (name "unconnected-(U14-TEST-Pad32)") (class "Default")
      (node (ref "U14") (pin "32") (pinfunction "TEST_32") (pintype "passive+no_connect"))
    )
  )
)
